# CAN.net
KiCad netlist of a schematic drawn in Altium Designer
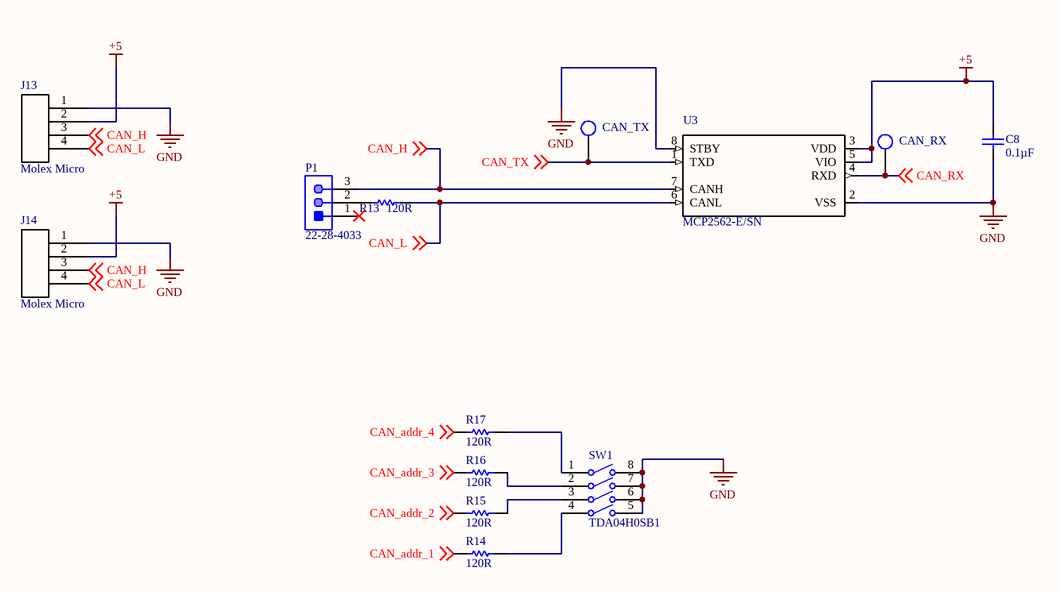
[diagram p0: CAN.SchDoc]

(export (version "E")
  (design (tool "Eeschema 10.0.6"))
  (components
    (comp (ref "C8")
      (value "Capacitor 0805")
      (footprint "Cap 0805")
      (description "Standard Capacitor")
      (fields (field (name "MANUFACTURER") "AVX") (field (name "CAPACITANCE") "0.1µF"))
      (libsource (lib "Standard Cap") (part "Capacitor 0805"))
    )
    (comp (ref "CAN_RX")
      (value "Test Point")
      (footprint "Test Point Through-hole")
      (libsource (lib "Husky Robotics Standard Library 2019-2020") (part "Test Point"))
    )
    (comp (ref "CAN_TX")
      (value "Test Point")
      (footprint "Test Point Through-hole")
      (libsource (lib "Husky Robotics Standard Library 2019-2020") (part "Test Point"))
    )
    (comp (ref "J13")
      (value "Molex Micro")
      (footprint "MICROFIT R/A 4 PIN")
      (description "Molex micro-fit 3.0 dual row header. P/N 0430450427")
      (libsource (lib "Husky Robotics Standard Library 2019-2020") (part "Molex micro-fit 4-pin (Single row schematic)"))
    )
    (comp (ref "J14")
      (value "Molex Micro")
      (footprint "MICROFIT R/A 4 PIN")
      (description "Molex micro-fit 3.0 dual row header. P/N 0430450427")
      (libsource (lib "Husky Robotics Standard Library 2019-2020") (part "Molex micro-fit 4-pin (Single row schematic)"))
    )
    (comp (ref "P1")
      (value "22-28-4033")
      (footprint "MOLX-22-28-4033_V")
      (description "Male Header, Pitch 2.54 mm, 1 x 3 Position, Height 8.38 mm, Tail Length 3.18 mm, RoHS, Bulk")
      (fields (field (name "MANUFACTURER") "Molex"))
      (libsource (lib "Altium Content Vault") (part "CN-1P-M-R3"))
    )
    (comp (ref "R13")
      (value "120R")
      (footprint "RESC0805(2012)_N")
      (description "Generic 0805 Resistor")
      (fields (field (name "TOLERANCE") "5 %") (field (name "POWER") "0.125 W"))
      (libsource (lib "Husky Robotics Standard Library 2019-2020") (part "Resistor 0805"))
    )
    (comp (ref "R14")
      (value "120R")
      (footprint "RESC0805(2012)_N")
      (description "Generic 0805 Resistor")
      (fields (field (name "TOLERANCE") "5 %") (field (name "POWER") "0.125 W"))
      (libsource (lib "Husky Robotics Standard Library 2019-2020") (part "Resistor 0805"))
    )
    (comp (ref "R15")
      (value "120R")
      (footprint "RESC0805(2012)_N")
      (description "Generic 0805 Resistor")
      (fields (field (name "TOLERANCE") "5 %") (field (name "POWER") "0.125 W"))
      (libsource (lib "Husky Robotics Standard Library 2019-2020") (part "Resistor 0805"))
    )
    (comp (ref "R16")
      (value "120R")
      (footprint "RESC0805(2012)_N")
      (description "Generic 0805 Resistor")
      (fields (field (name "TOLERANCE") "5 %") (field (name "POWER") "0.125 W"))
      (libsource (lib "Husky Robotics Standard Library 2019-2020") (part "Resistor 0805"))
    )
    (comp (ref "R17")
      (value "120R")
      (footprint "RESC0805(2012)_N")
      (description "Generic 0805 Resistor")
      (fields (field (name "TOLERANCE") "5 %") (field (name "POWER") "0.125 W"))
      (libsource (lib "Husky Robotics Standard Library 2019-2020") (part "Resistor 0805"))
    )
    (comp (ref "SW1")
      (value "TDA04H0SB1")
      (footprint "CKCP-TDA04H0SB1R_V")
      (fields (field (name "DIGI-KEY_PART_NUMBER") "CKN9065-ND"))
      (libsource (lib "DIP Switch Arrays") (part "Dip Switch Array SMD Half-Pitch"))
    )
    (comp (ref "U3")
      (value "MCP2562-E/SN")
      (footprint "SOIC127P600X175-8N")
      (description "Microchip MCP2562-E/SN, CAN Transceiver 1MBps 1-channel IEC 61000-4-2, 8-Pin SOIC")
      (fields (field (name "MF") "Microchip"))
      (libsource (lib "Husky Robotics Standard Library 2019-2020") (part "CAN Tranceiver"))
    )
  )
  (nets
    (net (code "1") (name "+5") (class "Default")
      (node (ref "C8") (pin "2") (pinfunction "2_2") (pintype "passive"))
      (node (ref "J13") (pin "2") (pintype "passive"))
      (node (ref "J14") (pin "2") (pintype "passive"))
      (node (ref "U3") (pin "3") (pinfunction "VDD_3") (pintype "power_in"))
      (node (ref "U3") (pin "5") (pinfunction "VIO_5") (pintype "power_in"))
    )
    (net (code "2") (name "CAN_H") (class "Default")
      (node (ref "J13") (pin "3") (pintype "passive"))
      (node (ref "J14") (pin "3") (pintype "passive"))
      (node (ref "P1") (pin "3") (pinfunction "3_3") (pintype "passive"))
      (node (ref "U3") (pin "7") (pinfunction "CANH_7") (pintype "input"))
    )
    (net (code "3") (name "CAN_L") (class "Default")
      (node (ref "J13") (pin "4") (pintype "passive"))
      (node (ref "J14") (pin "4") (pintype "passive"))
      (node (ref "R13") (pin "2") (pinfunction "2_2") (pintype "passive"))
      (node (ref "U3") (pin "6") (pinfunction "CANL_6") (pintype "input"))
    )
    (net (code "4") (name "CAN_RX") (class "Default")
      (node (ref "CAN_RX") (pin "1") (pinfunction "1_1") (pintype "passive"))
      (node (ref "U3") (pin "4") (pinfunction "RXD_4") (pintype "output"))
    )
    (net (code "5") (name "CAN_TX") (class "Default")
      (node (ref "CAN_TX") (pin "1") (pinfunction "1_1") (pintype "passive"))
      (node (ref "U3") (pin "1") (pinfunction "TXD_1") (pintype "input"))
    )
    (net (code "6") (name "CAN_addr_1") (class "Default")
      (node (ref "R14") (pin "1") (pinfunction "1_1") (pintype "passive"))
    )
    (net (code "7") (name "CAN_addr_2") (class "Default")
      (node (ref "R15") (pin "1") (pinfunction "1_1") (pintype "passive"))
    )
    (net (code "8") (name "CAN_addr_3") (class "Default")
      (node (ref "R16") (pin "1") (pinfunction "1_1") (pintype "passive"))
    )
    (net (code "9") (name "CAN_addr_4") (class "Default")
      (node (ref "R17") (pin "1") (pinfunction "1_1") (pintype "passive"))
    )
    (net (code "10") (name "GND") (class "Default")
      (node (ref "C8") (pin "1") (pinfunction "1_1") (pintype "passive"))
      (node (ref "J13") (pin "1") (pintype "passive"))
      (node (ref "J14") (pin "1") (pintype "passive"))
      (node (ref "SW1") (pin "5") (pinfunction "5_5") (pintype "passive"))
      (node (ref "SW1") (pin "6") (pinfunction "6_6") (pintype "passive"))
      (node (ref "SW1") (pin "7") (pinfunction "7_7") (pintype "passive"))
      (node (ref "SW1") (pin "8") (pinfunction "8_8") (pintype "passive"))
      (node (ref "U3") (pin "2") (pinfunction "VSS_2") (pintype "power_in"))
      (node (ref "U3") (pin "8") (pinfunction "STBY_8") (pintype "input"))
    )
    (net (code "11") (name "Net-(P1-Pad2)") (class "Default")
      (node (ref "P1") (pin "2") (pinfunction "2_2") (pintype "passive"))
      (node (ref "R13") (pin "1") (pinfunction "1_1") (pintype "passive"))
    )
    (net (code "12") (name "Net-(R14-Pad2)") (class "Default")
      (node (ref "R14") (pin "2") (pinfunction "2_2") (pintype "passive"))
      (node (ref "SW1") (pin "4") (pinfunction "4_4") (pintype "passive"))
    )
    (net (code "13") (name "Net-(R15-Pad2)") (class "Default")
      (node (ref "R15") (pin "2") (pinfunction "2_2") (pintype "passive"))
      (node (ref "SW1") (pin "3") (pinfunction "3_3") (pintype "passive"))
    )
    (net (code "14") (name "Net-(R16-Pad2)") (class "Default")
      (node (ref "R16") (pin "2") (pinfunction "2_2") (pintype "passive"))
      (node (ref "SW1") (pin "2") (pinfunction "2_2") (pintype "passive"))
    )
    (net (code "15") (name "Net-(R17-Pad2)") (class "Default")
      (node (ref "R17") (pin "2") (pinfunction "2_2") (pintype "passive"))
      (node (ref "SW1") (pin "1") (pinfunction "1_1") (pintype "passive"))
    )
    (net (code "16") (name "unconnected-(P1-Pad1)") (class "Default")
      (node (ref "P1") (pin "1") (pinfunction "1_1") (pintype "passive+no_connect"))
    )
  )
)
